# C116.net
KiCad netlist of a schematic drawn in EasyEDA Pro
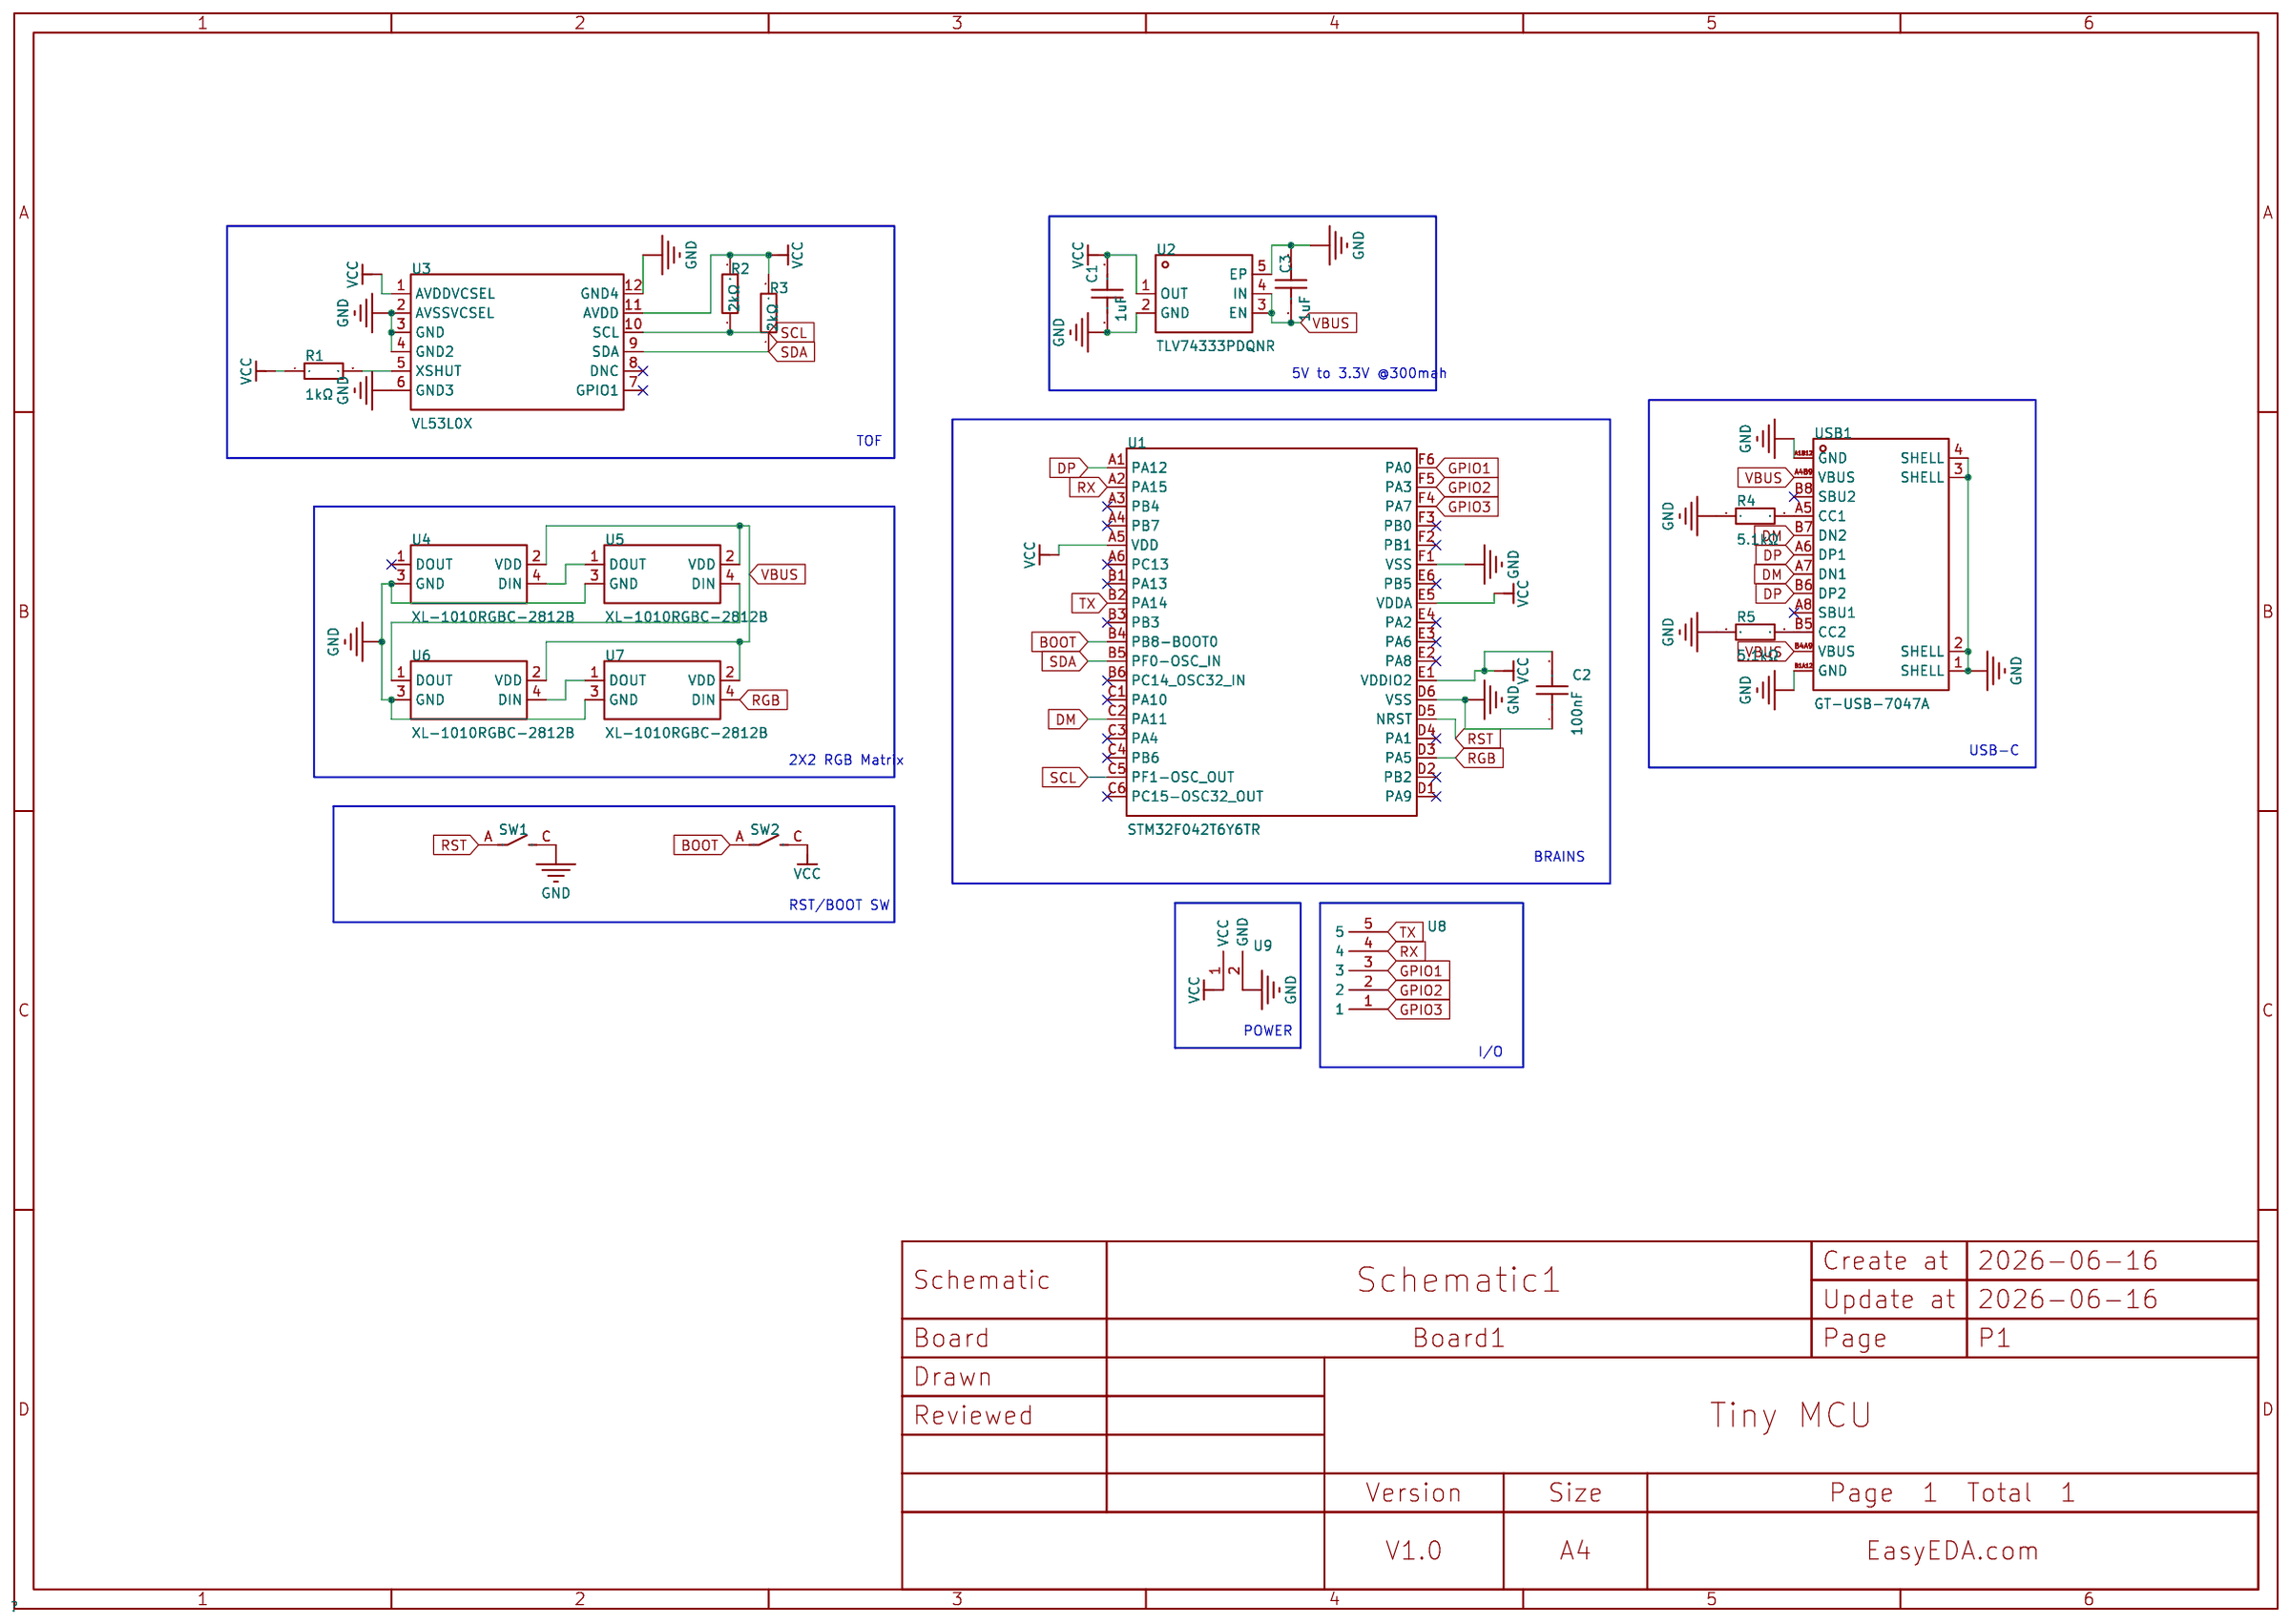
[diagram p0: schematic sheet]

(export (version "E")
  (design (tool "Eeschema 10.0.6"))
  (components
    (comp (ref "C1")
      (value "1uF")
      (footprint "easyedapro:C0201")
      (fields (field (name "Manufacturer Part") "0201X105M6R3CT") (field (name "Manufacturer") "Walsin(华新科)"))
      (libsource (lib "easyedapro") (part "0201X105M6R3CT"))
    )
    (comp (ref "C2")
      (value "100nF")
      (footprint "easyedapro:C0201")
      (fields
        (field (name "Manufacturer Part") "GRM033C71C104KE14J")
        (field (name "Manufacturer") "muRata(村田)")
      )
      (libsource (lib "easyedapro") (part "GRM033C71C104KE14J"))
    )
    (comp (ref "C3")
      (value "1uF")
      (footprint "easyedapro:C0201")
      (fields (field (name "Manufacturer Part") "0201X105M6R3CT") (field (name "Manufacturer") "Walsin(华新科)"))
      (libsource (lib "easyedapro") (part "0201X105M6R3CT"))
    )
    (comp (ref "R1")
      (value "1kΩ")
      (footprint "easyedapro:R0201")
      (fields (field (name "Manufacturer Part") "CR0201JH0102G") (field (name "Manufacturer") "LIZ(丽智电子)"))
      (libsource (lib "easyedapro") (part "CR0201JH0102G"))
    )
    (comp (ref "R2")
      (value "2kΩ")
      (footprint "easyedapro:R0201")
      (fields (field (name "Manufacturer Part") "CR0201JH0202G") (field (name "Manufacturer") "LIZ(丽智电子)"))
      (libsource (lib "easyedapro") (part "CR0201JH0202G"))
    )
    (comp (ref "R3")
      (value "2kΩ")
      (footprint "easyedapro:R0201")
      (fields (field (name "Manufacturer Part") "CR0201JH0202G") (field (name "Manufacturer") "LIZ(丽智电子)"))
      (libsource (lib "easyedapro") (part "CR0201JH0202G"))
    )
    (comp (ref "R4")
      (value "5.1kΩ")
      (footprint "easyedapro:R0201")
      (fields (field (name "Manufacturer Part") "RC0201JR-075K1L") (field (name "Manufacturer") "YAGEO(国巨)"))
      (libsource (lib "easyedapro") (part "RC0201JR-075K1L"))
    )
    (comp (ref "R5")
      (value "5.1kΩ")
      (footprint "easyedapro:R0201")
      (fields (field (name "Manufacturer Part") "RC0201JR-075K1L") (field (name "Manufacturer") "YAGEO(国巨)"))
      (libsource (lib "easyedapro") (part "RC0201JR-075K1L"))
    )
    (comp (ref "SW1")
      (value "GT-TC194A-H0055-L1")
      (footprint "easyedapro:SW-SMD_4P-L2.5-W1.6-LS2.9_STI-055A12AX")
      (fields (field (name "Manufacturer") "G-Switch(品赞)"))
      (libsource (lib "easyedapro") (part "GT-TC194A-H0055-L1"))
    )
    (comp (ref "SW2")
      (value "GT-TC194A-H0055-L1")
      (footprint "easyedapro:SW-SMD_4P-L2.5-W1.6-LS2.9_STI-055A12AX")
      (fields (field (name "Manufacturer") "G-Switch(品赞)"))
      (libsource (lib "easyedapro") (part "GT-TC194A-H0055-L1"))
    )
    (comp (ref "U1")
      (value "STM32F042T6Y6TR")
      (footprint "easyedapro:WLCSP-36_L2.7-W2.6-R-C6-P0.40-BL")
      (fields (field (name "Manufacturer") "ST(意法半导体)"))
      (libsource (lib "easyedapro") (part "STM32F042T6Y6TR"))
    )
    (comp (ref "U2")
      (value "TLV74333PDQNR")
      (footprint "easyedapro:X2SON-4_L1.0-W1.0-P0.65-TL-EP")
      (fields (field (name "Manufacturer") "TI(德州仪器)"))
      (libsource (lib "easyedapro") (part "TLV74333PDQNR"))
    )
    (comp (ref "U3")
      (value "VL53L0X")
      (footprint "easyedapro:LGA-12_L4.4-W2.4_VL53L0X")
      (libsource (lib "easyedapro") (part "VL53L0X"))
    )
    (comp (ref "U4")
      (value "XL-1010RGBC-2812B")
      (footprint "easyedapro:LED-SMD_4P-L1.0-W1.0-TL_XL-1010RGBC-WS2812B")
      (fields (field (name "Manufacturer") "XINGLIGHT(成兴光)"))
      (libsource (lib "easyedapro") (part "XL-1010RGBC-WS2812B"))
    )
    (comp (ref "U5")
      (value "XL-1010RGBC-2812B")
      (footprint "easyedapro:LED-SMD_4P-L1.0-W1.0-TL_XL-1010RGBC-WS2812B")
      (fields (field (name "Manufacturer") "XINGLIGHT(成兴光)"))
      (libsource (lib "easyedapro") (part "XL-1010RGBC-WS2812B"))
    )
    (comp (ref "U6")
      (value "XL-1010RGBC-2812B")
      (footprint "easyedapro:LED-SMD_4P-L1.0-W1.0-TL_XL-1010RGBC-WS2812B")
      (fields (field (name "Manufacturer") "XINGLIGHT(成兴光)"))
      (libsource (lib "easyedapro") (part "XL-1010RGBC-WS2812B"))
    )
    (comp (ref "U7")
      (value "XL-1010RGBC-2812B")
      (footprint "easyedapro:LED-SMD_4P-L1.0-W1.0-TL_XL-1010RGBC-WS2812B")
      (fields (field (name "Manufacturer") "XINGLIGHT(成兴光)"))
      (libsource (lib "easyedapro") (part "XL-1010RGBC-WS2812B"))
    )
    (comp (ref "U8")
      (value "~")
      (footprint "easyedapro:PAD'S")
      (libsource (lib "easyedapro") (part "pad's for tiny mcu"))
    )
    (comp (ref "U9")
      (value "~")
      (footprint "easyedapro:POWER PADS")
      (libsource (lib "easyedapro") (part "POWER PAD'S"))
    )
    (comp (ref "USB1")
      (value "GT-USB-7047A")
      (footprint "easyedapro:USB-C-SMD_GT-USB-7047A")
      (fields (field (name "Manufacturer") "G-Switch(品赞)"))
      (libsource (lib "easyedapro") (part "GT-USB-7047A"))
    )
  )
  (nets
    (net (code "1") (name "BOOT") (class "Default")
      (node (ref "SW2") (pin "A") (pinfunction "A_A") (pintype "unspecified"))
      (node (ref "U1") (pin "B4") (pinfunction "PB8-BOOT0_B4") (pintype "unspecified"))
    )
    (net (code "2") (name "DM") (class "Default")
      (node (ref "U1") (pin "C2") (pinfunction "PA11_C2") (pintype "unspecified"))
      (node (ref "USB1") (pin "A7") (pinfunction "DN1_A7") (pintype "unspecified"))
      (node (ref "USB1") (pin "B7") (pinfunction "DN2_B7") (pintype "unspecified"))
    )
    (net (code "3") (name "DP") (class "Default")
      (node (ref "U1") (pin "A1") (pinfunction "PA12_A1") (pintype "unspecified"))
      (node (ref "USB1") (pin "A6") (pinfunction "DP1_A6") (pintype "unspecified"))
      (node (ref "USB1") (pin "B6") (pinfunction "DP2_B6") (pintype "unspecified"))
    )
    (net (code "4") (name "GND") (class "Default")
      (node (ref "C1") (pin "1") (pinfunction "1_1") (pintype "unspecified"))
      (node (ref "C2") (pin "1") (pinfunction "1_1") (pintype "unspecified"))
      (node (ref "C3") (pin "2") (pinfunction "2_2") (pintype "unspecified"))
      (node (ref "R4") (pin "1") (pinfunction "1_1") (pintype "unspecified"))
      (node (ref "R5") (pin "1") (pinfunction "1_1") (pintype "unspecified"))
      (node (ref "SW1") (pin "C") (pinfunction "C_C") (pintype "unspecified"))
      (node (ref "U1") (pin "D6") (pinfunction "VSS_D6") (pintype "unspecified"))
      (node (ref "U1") (pin "F1") (pinfunction "VSS_F1") (pintype "unspecified"))
      (node (ref "U2") (pin "2") (pinfunction "GND_2") (pintype "unspecified"))
      (node (ref "U2") (pin "5") (pinfunction "EP_5") (pintype "unspecified"))
      (node (ref "U3") (pin "12") (pinfunction "GND4_12") (pintype "unspecified"))
      (node (ref "U3") (pin "2") (pinfunction "AVSSVCSEL_2") (pintype "unspecified"))
      (node (ref "U3") (pin "3") (pinfunction "GND_3") (pintype "unspecified"))
      (node (ref "U3") (pin "4") (pinfunction "GND2_4") (pintype "unspecified"))
      (node (ref "U3") (pin "6") (pinfunction "GND3_6") (pintype "unspecified"))
      (node (ref "U4") (pin "3") (pinfunction "GND_3") (pintype "unspecified"))
      (node (ref "U5") (pin "3") (pinfunction "GND_3") (pintype "unspecified"))
      (node (ref "U6") (pin "3") (pinfunction "GND_3") (pintype "unspecified"))
      (node (ref "U7") (pin "3") (pinfunction "GND_3") (pintype "unspecified"))
      (node (ref "U9") (pin "2") (pinfunction "GND_2") (pintype "unspecified"))
      (node (ref "USB1") (pin "1") (pinfunction "SHELL_1") (pintype "unspecified"))
      (node (ref "USB1") (pin "2") (pinfunction "SHELL_2") (pintype "unspecified"))
      (node (ref "USB1") (pin "3") (pinfunction "SHELL_3") (pintype "unspecified"))
      (node (ref "USB1") (pin "4") (pinfunction "SHELL_4") (pintype "unspecified"))
      (node (ref "USB1") (pin "A1B12") (pinfunction "GND_A1B12") (pintype "unspecified"))
      (node (ref "USB1") (pin "B1A12") (pinfunction "GND_B1A12") (pintype "unspecified"))
    )
    (net (code "5") (name "GPIO1") (class "Default")
      (node (ref "U1") (pin "F6") (pinfunction "PA0_F6") (pintype "unspecified"))
      (node (ref "U8") (pin "3") (pinfunction "3_3") (pintype "unspecified"))
    )
    (net (code "6") (name "GPIO2") (class "Default")
      (node (ref "U1") (pin "F5") (pinfunction "PA3_F5") (pintype "unspecified"))
      (node (ref "U8") (pin "2") (pinfunction "2_2") (pintype "unspecified"))
    )
    (net (code "7") (name "GPIO3") (class "Default")
      (node (ref "U1") (pin "F4") (pinfunction "PA7_F4") (pintype "unspecified"))
      (node (ref "U8") (pin "1") (pinfunction "1_1") (pintype "unspecified"))
    )
    (net (code "8") (name "Net-(U3-XSHUT)") (class "Default")
      (node (ref "R1") (pin "2") (pinfunction "2_2") (pintype "input"))
      (node (ref "U3") (pin "5") (pinfunction "XSHUT_5") (pintype "unspecified"))
    )
    (net (code "9") (name "Net-(U4-DIN)") (class "Default")
      (node (ref "U4") (pin "4") (pinfunction "DIN_4") (pintype "unspecified"))
      (node (ref "U5") (pin "1") (pinfunction "DOUT_1") (pintype "unspecified"))
    )
    (net (code "10") (name "Net-(U5-DIN)") (class "Default")
      (node (ref "U5") (pin "4") (pinfunction "DIN_4") (pintype "unspecified"))
      (node (ref "U6") (pin "1") (pinfunction "DOUT_1") (pintype "unspecified"))
    )
    (net (code "11") (name "Net-(U6-DIN)") (class "Default")
      (node (ref "U6") (pin "4") (pinfunction "DIN_4") (pintype "unspecified"))
      (node (ref "U7") (pin "1") (pinfunction "DOUT_1") (pintype "unspecified"))
    )
    (net (code "12") (name "Net-(USB1-CC1)") (class "Default")
      (node (ref "R4") (pin "2") (pinfunction "2_2") (pintype "unspecified"))
      (node (ref "USB1") (pin "A5") (pinfunction "CC1_A5") (pintype "unspecified"))
    )
    (net (code "13") (name "Net-(USB1-CC2)") (class "Default")
      (node (ref "R5") (pin "2") (pinfunction "2_2") (pintype "unspecified"))
      (node (ref "USB1") (pin "B5") (pinfunction "CC2_B5") (pintype "unspecified"))
    )
    (net (code "14") (name "RGB") (class "Default")
      (node (ref "U1") (pin "D3") (pinfunction "PA5_D3") (pintype "unspecified"))
      (node (ref "U7") (pin "4") (pinfunction "DIN_4") (pintype "unspecified"))
    )
    (net (code "15") (name "RST") (class "Default")
      (node (ref "SW1") (pin "A") (pinfunction "A_A") (pintype "unspecified"))
      (node (ref "U1") (pin "D5") (pinfunction "NRST_D5") (pintype "unspecified"))
    )
    (net (code "16") (name "RX") (class "Default")
      (node (ref "U1") (pin "A2") (pinfunction "PA15_A2") (pintype "unspecified"))
      (node (ref "U8") (pin "4") (pinfunction "4_4") (pintype "unspecified"))
    )
    (net (code "17") (name "SCL") (class "Default")
      (node (ref "R2") (pin "1") (pinfunction "1_1") (pintype "unspecified"))
      (node (ref "U1") (pin "C5") (pinfunction "PF1-OSC_OUT_C5") (pintype "unspecified"))
      (node (ref "U3") (pin "10") (pinfunction "SCL_10") (pintype "unspecified"))
    )
    (net (code "18") (name "SDA") (class "Default")
      (node (ref "R3") (pin "1") (pinfunction "1_1") (pintype "unspecified"))
      (node (ref "U1") (pin "B5") (pinfunction "PF0-OSC_IN_B5") (pintype "unspecified"))
      (node (ref "U3") (pin "9") (pinfunction "SDA_9") (pintype "unspecified"))
    )
    (net (code "19") (name "TX") (class "Default")
      (node (ref "U1") (pin "B2") (pinfunction "PA14_B2") (pintype "unspecified"))
      (node (ref "U8") (pin "5") (pinfunction "5_5") (pintype "unspecified"))
    )
    (net (code "20") (name "VBUS") (class "Default")
      (node (ref "C3") (pin "1") (pinfunction "1_1") (pintype "unspecified"))
      (node (ref "U2") (pin "3") (pinfunction "EN_3") (pintype "unspecified"))
      (node (ref "U2") (pin "4") (pinfunction "IN_4") (pintype "unspecified"))
      (node (ref "U4") (pin "2") (pinfunction "VDD_2") (pintype "unspecified"))
      (node (ref "U5") (pin "2") (pinfunction "VDD_2") (pintype "unspecified"))
      (node (ref "U6") (pin "2") (pinfunction "VDD_2") (pintype "unspecified"))
      (node (ref "U7") (pin "2") (pinfunction "VDD_2") (pintype "unspecified"))
      (node (ref "USB1") (pin "A4B9") (pinfunction "VBUS_A4B9") (pintype "unspecified"))
      (node (ref "USB1") (pin "B4A9") (pinfunction "VBUS_B4A9") (pintype "unspecified"))
    )
    (net (code "21") (name "VCC") (class "Default")
      (node (ref "C1") (pin "2") (pinfunction "2_2") (pintype "unspecified"))
      (node (ref "C2") (pin "2") (pinfunction "2_2") (pintype "unspecified"))
      (node (ref "R1") (pin "1") (pinfunction "1_1") (pintype "input"))
      (node (ref "R2") (pin "2") (pinfunction "2_2") (pintype "unspecified"))
      (node (ref "R3") (pin "2") (pinfunction "2_2") (pintype "unspecified"))
      (node (ref "SW2") (pin "C") (pinfunction "C_C") (pintype "unspecified"))
      (node (ref "U1") (pin "A5") (pinfunction "VDD_A5") (pintype "unspecified"))
      (node (ref "U1") (pin "E1") (pinfunction "VDDIO2_E1") (pintype "unspecified"))
      (node (ref "U1") (pin "E5") (pinfunction "VDDA_E5") (pintype "unspecified"))
      (node (ref "U2") (pin "1") (pinfunction "OUT_1") (pintype "unspecified"))
      (node (ref "U3") (pin "1") (pinfunction "AVDDVCSEL_1") (pintype "unspecified"))
      (node (ref "U3") (pin "11") (pinfunction "AVDD_11") (pintype "unspecified"))
      (node (ref "U9") (pin "1") (pinfunction "VCC_1") (pintype "unspecified"))
    )
    (net (code "22") (name "unconnected-(U1-PA1-PadD4)") (class "Default")
      (node (ref "U1") (pin "D4") (pinfunction "PA1_D4") (pintype "unspecified+no_connect"))
    )
    (net (code "23") (name "unconnected-(U1-PA2-PadE4)") (class "Default")
      (node (ref "U1") (pin "E4") (pinfunction "PA2_E4") (pintype "unspecified+no_connect"))
    )
    (net (code "24") (name "unconnected-(U1-PA4-PadC3)") (class "Default")
      (node (ref "U1") (pin "C3") (pinfunction "PA4_C3") (pintype "unspecified+no_connect"))
    )
    (net (code "25") (name "unconnected-(U1-PA6-PadE3)") (class "Default")
      (node (ref "U1") (pin "E3") (pinfunction "PA6_E3") (pintype "unspecified+no_connect"))
    )
    (net (code "26") (name "unconnected-(U1-PA8-PadE2)") (class "Default")
      (node (ref "U1") (pin "E2") (pinfunction "PA8_E2") (pintype "unspecified+no_connect"))
    )
    (net (code "27") (name "unconnected-(U1-PA9-PadD1)") (class "Default")
      (node (ref "U1") (pin "D1") (pinfunction "PA9_D1") (pintype "unspecified+no_connect"))
    )
    (net (code "28") (name "unconnected-(U1-PA10-PadC1)") (class "Default")
      (node (ref "U1") (pin "C1") (pinfunction "PA10_C1") (pintype "unspecified+no_connect"))
    )
    (net (code "29") (name "unconnected-(U1-PA13-PadB1)") (class "Default")
      (node (ref "U1") (pin "B1") (pinfunction "PA13_B1") (pintype "unspecified+no_connect"))
    )
    (net (code "30") (name "unconnected-(U1-PB0-PadF3)") (class "Default")
      (node (ref "U1") (pin "F3") (pinfunction "PB0_F3") (pintype "unspecified+no_connect"))
    )
    (net (code "31") (name "unconnected-(U1-PB1-PadF2)") (class "Default")
      (node (ref "U1") (pin "F2") (pinfunction "PB1_F2") (pintype "unspecified+no_connect"))
    )
    (net (code "32") (name "unconnected-(U1-PB2-PadD2)") (class "Default")
      (node (ref "U1") (pin "D2") (pinfunction "PB2_D2") (pintype "unspecified+no_connect"))
    )
    (net (code "33") (name "unconnected-(U1-PB3-PadB3)") (class "Default")
      (node (ref "U1") (pin "B3") (pinfunction "PB3_B3") (pintype "unspecified+no_connect"))
    )
    (net (code "34") (name "unconnected-(U1-PB4-PadA3)") (class "Default")
      (node (ref "U1") (pin "A3") (pinfunction "PB4_A3") (pintype "unspecified+no_connect"))
    )
    (net (code "35") (name "unconnected-(U1-PB5-PadE6)") (class "Default")
      (node (ref "U1") (pin "E6") (pinfunction "PB5_E6") (pintype "unspecified+no_connect"))
    )
    (net (code "36") (name "unconnected-(U1-PB6-PadC4)") (class "Default")
      (node (ref "U1") (pin "C4") (pinfunction "PB6_C4") (pintype "unspecified+no_connect"))
    )
    (net (code "37") (name "unconnected-(U1-PB7-PadA4)") (class "Default")
      (node (ref "U1") (pin "A4") (pinfunction "PB7_A4") (pintype "unspecified+no_connect"))
    )
    (net (code "38") (name "unconnected-(U1-PC13-PadA6)") (class "Default")
      (node (ref "U1") (pin "A6") (pinfunction "PC13_A6") (pintype "unspecified+no_connect"))
    )
    (net (code "39") (name "unconnected-(U1-PC14_OSC32_IN-PadB6)") (class "Default")
      (node (ref "U1") (pin "B6") (pinfunction "PC14_OSC32_IN_B6") (pintype "unspecified+no_connect"))
    )
    (net (code "40") (name "unconnected-(U1-PC15-OSC32_OUT-PadC6)") (class "Default")
      (node (ref "U1") (pin "C6") (pinfunction "PC15-OSC32_OUT_C6") (pintype "unspecified+no_connect"))
    )
    (net (code "41") (name "unconnected-(U3-DNC-Pad8)") (class "Default")
      (node (ref "U3") (pin "8") (pinfunction "DNC_8") (pintype "unspecified+no_connect"))
    )
    (net (code "42") (name "unconnected-(U3-GPIO1-Pad7)") (class "Default")
      (node (ref "U3") (pin "7") (pinfunction "GPIO1_7") (pintype "unspecified+no_connect"))
    )
    (net (code "43") (name "unconnected-(U4-DOUT-Pad1)") (class "Default")
      (node (ref "U4") (pin "1") (pinfunction "DOUT_1") (pintype "unspecified+no_connect"))
    )
    (net (code "44") (name "unconnected-(USB1-SBU1-PadA8)") (class "Default")
      (node (ref "USB1") (pin "A8") (pinfunction "SBU1_A8") (pintype "unspecified+no_connect"))
    )
    (net (code "45") (name "unconnected-(USB1-SBU2-PadB8)") (class "Default")
      (node (ref "USB1") (pin "B8") (pinfunction "SBU2_B8") (pintype "unspecified+no_connect"))
    )
  )
)
